# FAN.net
KiCad netlist of a schematic drawn in Altium Designer
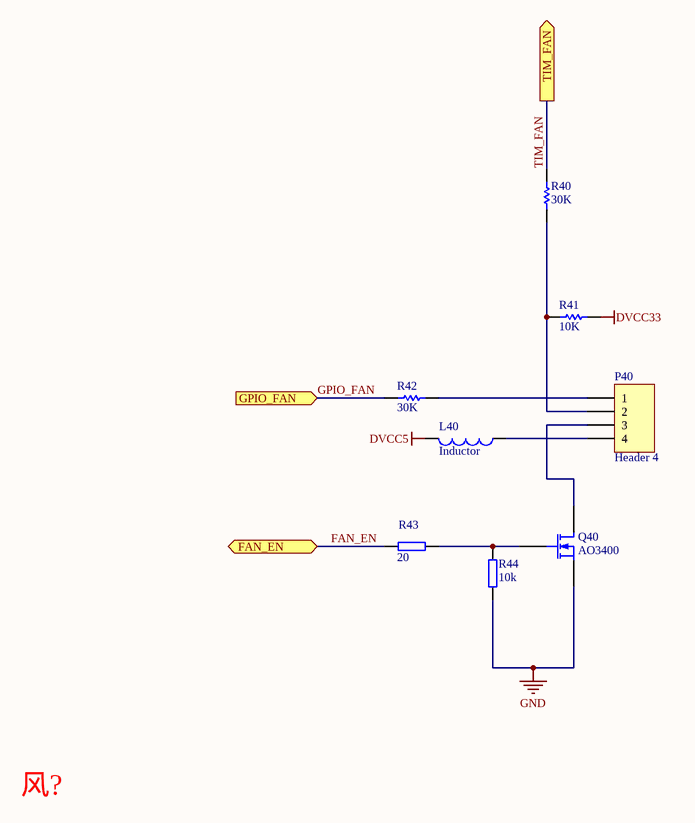
[diagram p0: FAN.SchDoc]

(export (version "E")
  (design (tool "Eeschema 10.0.6"))
  (components
    (comp (ref "L40")
      (value "Inductor")
      (footprint "L0402")
      (fields (field (name "PUBLISHER") "Altium Limited"))
      (libsource (lib "Miscellaneous Devices") (part "Inductor"))
    )
    (comp (ref "P40")
      (value "Header 4")
      (footprint "1.5P-4")
      (description "Header, 4-Pin")
      (fields (field (name "PUBLISHER") "Altium Limited"))
      (libsource (lib "Miscellaneous Connectors") (part "Header 4"))
    )
    (comp (ref "Q40")
      (value "AO3400")
      (footprint "SI2300")
      (description "N-Channel MOSFET")
      (libsource (lib "Miscellaneous Devices") (part "MOSFET-N"))
    )
    (comp (ref "R40")
      (value "30K")
      (footprint "R0402")
      (description "Resistor 0402")
      (fields (field (name "PUBLISHER") "Altium Limited"))
      (libsource (lib "Resistances") (part "R0402"))
    )
    (comp (ref "R41")
      (value "10K")
      (footprint "R0402")
      (description "Resistor 0402")
      (fields (field (name "PUBLISHER") "Altium Limited"))
      (libsource (lib "Resistances") (part "R0402"))
    )
    (comp (ref "R42")
      (value "30K")
      (footprint "R0402")
      (description "Resistor 0402")
      (fields (field (name "PUBLISHER") "Altium Limited"))
      (libsource (lib "Resistances") (part "R0402"))
    )
    (comp (ref "R43") (value "20") (footprint "R0402") (libsource (lib "CxyDXP_SCH") (part "RES1")))
    (comp (ref "R44") (value "10k") (footprint "R0402") (libsource (lib "CxyDXP_SCH") (part "RES1")))
  )
  (nets
    (net (code "1") (name "/FAN_EN") (class "Default")
      (node (ref "R43") (pin "2") (pinfunction "2_2") (pintype "passive"))
    )
    (net (code "2") (name "/GPIO_FAN") (class "Default")
      (node (ref "R42") (pin "1") (pinfunction "1_1") (pintype "passive"))
    )
    (net (code "3") (name "/TIM_FAN") (class "Default")
      (node (ref "R40") (pin "2") (pinfunction "2_2") (pintype "passive"))
    )
    (net (code "4") (name "DVCC5") (class "Default")
      (node (ref "L40") (pin "2") (pinfunction "2_2") (pintype "passive"))
    )
    (net (code "5") (name "DVCC33") (class "Default")
      (node (ref "R41") (pin "1") (pinfunction "1_1") (pintype "passive"))
    )
    (net (code "6") (name "GND") (class "Default")
      (node (ref "Q40") (pin "3") (pinfunction "S_3") (pintype "passive"))
      (node (ref "R44") (pin "2") (pinfunction "2_2") (pintype "passive"))
    )
    (net (code "7") (name "Net-(L40-Pad1)") (class "Default")
      (node (ref "L40") (pin "1") (pinfunction "1_1") (pintype "passive"))
      (node (ref "P40") (pin "4") (pinfunction "4_4") (pintype "passive"))
    )
    (net (code "8") (name "Net-(P40-Pad1)") (class "Default")
      (node (ref "P40") (pin "1") (pinfunction "1_1") (pintype "passive"))
      (node (ref "R42") (pin "2") (pinfunction "2_2") (pintype "passive"))
    )
    (net (code "9") (name "Net-(P40-Pad2)") (class "Default")
      (node (ref "P40") (pin "2") (pinfunction "2_2") (pintype "passive"))
      (node (ref "R40") (pin "1") (pinfunction "1_1") (pintype "passive"))
      (node (ref "R41") (pin "2") (pinfunction "2_2") (pintype "passive"))
    )
    (net (code "10") (name "Net-(Q40-D)") (class "Default")
      (node (ref "P40") (pin "3") (pinfunction "3_3") (pintype "passive"))
      (node (ref "Q40") (pin "1") (pinfunction "D_1") (pintype "passive"))
    )
    (net (code "11") (name "Net-(Q40-G)") (class "Default")
      (node (ref "Q40") (pin "2") (pinfunction "G_2") (pintype "passive"))
      (node (ref "R43") (pin "1") (pinfunction "1_1") (pintype "passive"))
      (node (ref "R44") (pin "1") (pinfunction "1_1") (pintype "passive"))
    )
  )
)
